# PowerSupplies_old.net
KiCad netlist of a schematic drawn in Altium Designer
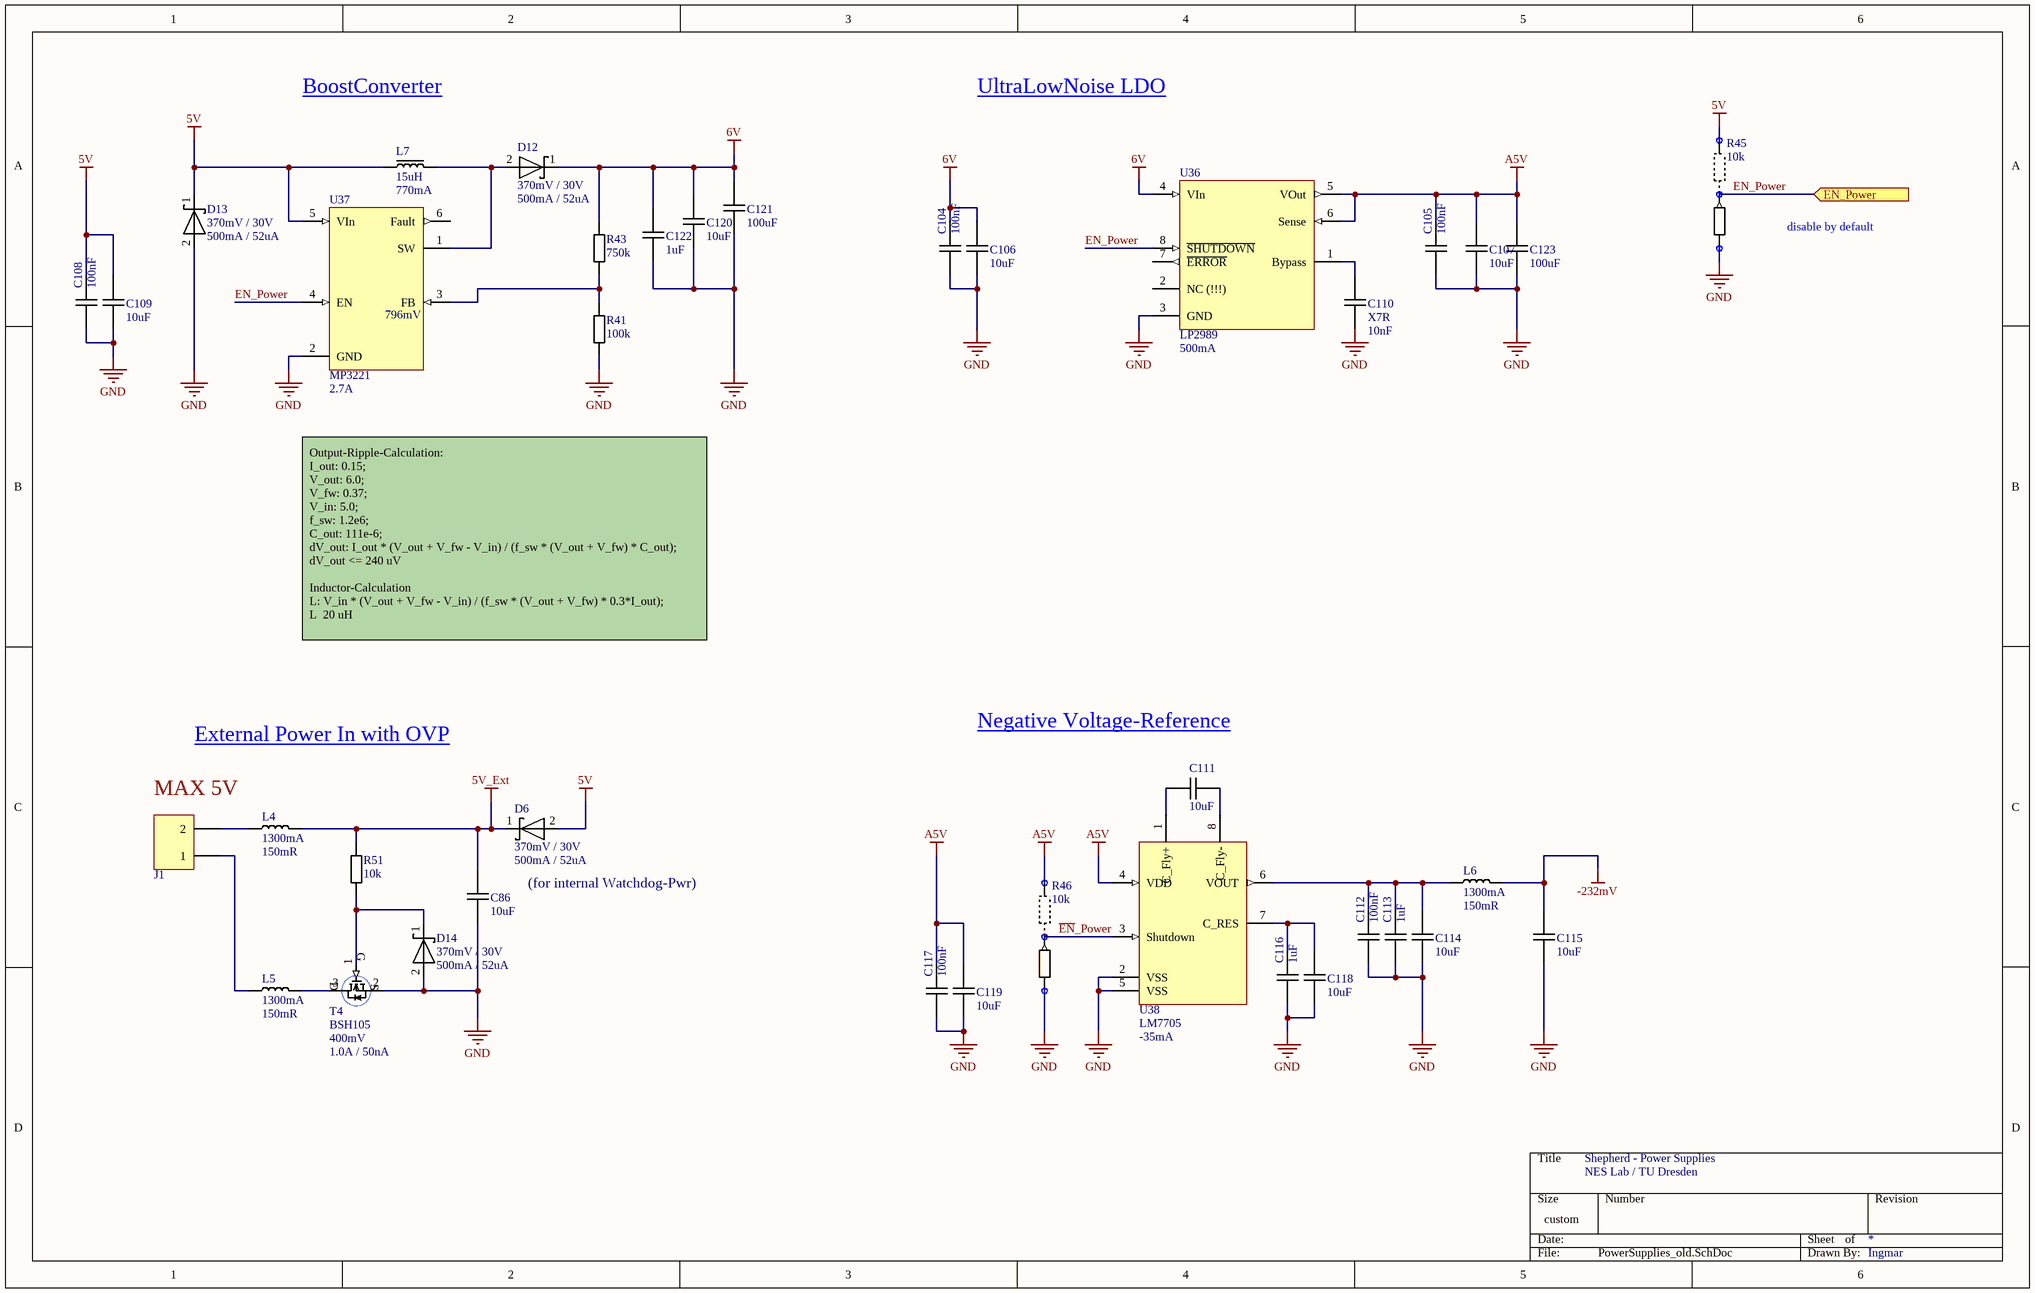
[diagram p0: PowerSupplies_old.SchDoc]

(export (version "E")
  (design (tool "Eeschema 10.0.6"))
  (components
    (comp (ref "C86")
      (value "10uF")
      (footprint "CAPC1608X09")
      (description "Capacitor")
      (fields (field (name "MANUFACTURER") "Murata") (field (name "TOLERANCE") "10%"))
      (libsource (lib "shepherd_parts") (part ".C_0603_10uF_6V3"))
    )
    (comp (ref "C104")
      (value "100nF")
      (footprint "CAPC1005X06")
      (description "Capacitor")
      (fields (field (name "MANUFACTURER") "Murata") (field (name "TOLERANCE") "10%"))
      (libsource (lib "shepherd_parts") (part ".C_0402_100nF_10V"))
    )
    (comp (ref "C105")
      (value "100nF")
      (footprint "CAPC1005X06")
      (description "Capacitor")
      (fields (field (name "MANUFACTURER") "Murata") (field (name "TOLERANCE") "10%"))
      (libsource (lib "shepherd_parts") (part ".C_0402_100nF_10V"))
    )
    (comp (ref "C106")
      (value "10uF")
      (footprint "CAPC1608X09")
      (description "Capacitor")
      (fields (field (name "MANUFACTURER") "Murata") (field (name "TOLERANCE") "10%"))
      (libsource (lib "shepherd_parts") (part ".C_0603_10uF_6V3"))
    )
    (comp (ref "C107")
      (value "10uF")
      (footprint "CAPC1608X09")
      (description "Capacitor")
      (fields (field (name "MANUFACTURER") "Murata") (field (name "TOLERANCE") "10%"))
      (libsource (lib "shepherd_parts") (part ".C_0603_10uF_6V3"))
    )
    (comp (ref "C108")
      (value "100nF")
      (footprint "CAPC1005X06")
      (description "Capacitor")
      (fields (field (name "MANUFACTURER") "Murata") (field (name "TOLERANCE") "10%"))
      (libsource (lib "shepherd_parts") (part ".C_0402_100nF_10V"))
    )
    (comp (ref "C109")
      (value "10uF")
      (footprint "CAPC1608X09")
      (description "Capacitor")
      (fields (field (name "MANUFACTURER") "Murata") (field (name "TOLERANCE") "10%"))
      (libsource (lib "shepherd_parts") (part ".C_0603_10uF_6V3"))
    )
    (comp (ref "C110")
      (value "10nF")
      (footprint "CAPC1005X06")
      (description "Capacitor")
      (fields
        (field (name "MANUFACTURER") "Murata")
        (field (name "TOLERANCE") "10%")
        (field (name "DIELECTRIC") "X7R")
      )
      (libsource (lib "shepherd_parts") (part ".C_0402_10nF_25V"))
    )
    (comp (ref "C111")
      (value "10uF")
      (footprint "CAPC1608X09")
      (description "Capacitor")
      (fields (field (name "MANUFACTURER") "Murata") (field (name "TOLERANCE") "10%"))
      (libsource (lib "shepherd_parts") (part ".C_0603_10uF_6V3"))
    )
    (comp (ref "C112")
      (value "100nF")
      (footprint "CAPC1005X06")
      (description "Capacitor")
      (fields (field (name "MANUFACTURER") "Murata") (field (name "TOLERANCE") "10%"))
      (libsource (lib "shepherd_parts") (part ".C_0402_100nF_10V"))
    )
    (comp (ref "C113")
      (value "1uF")
      (footprint "CAPC1608X09")
      (description "Capacitor")
      (fields (field (name "MANUFACTURER") "KEMET") (field (name "TOLERANCE") "10%"))
      (libsource (lib "shepherd_parts") (part ".C_0603_1uF_10V"))
    )
    (comp (ref "C114")
      (value "10uF")
      (footprint "CAPC1608X09")
      (description "Capacitor")
      (fields (field (name "MANUFACTURER") "Murata") (field (name "TOLERANCE") "10%"))
      (libsource (lib "shepherd_parts") (part ".C_0603_10uF_6V3"))
    )
    (comp (ref "C115")
      (value "10uF")
      (footprint "CAPC1608X09")
      (description "Capacitor")
      (fields (field (name "MANUFACTURER") "Murata") (field (name "TOLERANCE") "10%"))
      (libsource (lib "shepherd_parts") (part ".C_0603_10uF_6V3"))
    )
    (comp (ref "C116")
      (value "1uF")
      (footprint "CAPC1608X09")
      (description "Capacitor")
      (fields (field (name "MANUFACTURER") "KEMET") (field (name "TOLERANCE") "10%"))
      (libsource (lib "shepherd_parts") (part ".C_0603_1uF_10V"))
    )
    (comp (ref "C117")
      (value "100nF")
      (footprint "CAPC1005X06")
      (description "Capacitor")
      (fields (field (name "MANUFACTURER") "Murata") (field (name "TOLERANCE") "10%"))
      (libsource (lib "shepherd_parts") (part ".C_0402_100nF_10V"))
    )
    (comp (ref "C118")
      (value "10uF")
      (footprint "CAPC1608X09")
      (description "Capacitor")
      (fields (field (name "MANUFACTURER") "Murata") (field (name "TOLERANCE") "10%"))
      (libsource (lib "shepherd_parts") (part ".C_0603_10uF_6V3"))
    )
    (comp (ref "C119")
      (value "10uF")
      (footprint "CAPC1608X09")
      (description "Capacitor")
      (fields (field (name "MANUFACTURER") "Murata") (field (name "TOLERANCE") "10%"))
      (libsource (lib "shepherd_parts") (part ".C_0603_10uF_6V3"))
    )
    (comp (ref "C120")
      (value "10uF")
      (footprint "CAPC1608X09")
      (description "Capacitor")
      (fields (field (name "MANUFACTURER") "Murata") (field (name "TOLERANCE") "10%"))
      (libsource (lib "shepherd_parts") (part ".C_0603_10uF_6V3"))
    )
    (comp (ref "C121")
      (value "100uF")
      (footprint "CAPC3216X18")
      (description "Capacitor")
      (fields (field (name "MANUFACTURER") "Taiyo Yuden") (field (name "TOLERANCE") "20%"))
      (libsource (lib "shepherd_parts") (part ".C_1206_100uF_6V3"))
    )
    (comp (ref "C122")
      (value "1uF")
      (footprint "CAPC1608X09")
      (description "Capacitor")
      (fields (field (name "MANUFACTURER") "KEMET") (field (name "TOLERANCE") "10%"))
      (libsource (lib "shepherd_parts") (part ".C_0603_1uF_10V"))
    )
    (comp (ref "C123")
      (value "100uF")
      (footprint "CAPC3216X18")
      (description "Capacitor")
      (fields (field (name "MANUFACTURER") "Taiyo Yuden") (field (name "TOLERANCE") "20%"))
      (libsource (lib "shepherd_parts") (part ".C_1206_100uF_6V3"))
    )
    (comp (ref "D6")
      (value "370mV / 30V")
      (footprint "SODFL160X70-2N")
      (description "Diode Si, 370mV 500mA forward, 30V 52uA reverse, 3 A Surge,")
      (fields
        (field (name "MANUFACTURER") "On Semi")
        (field (name "I_MAX") "500mA / 52uA")
        (field (name "Comment") "D_SOD523_370mV_500mA")
      )
      (libsource (lib "shepherd_parts") (part ".D_SOD523_370mV_500mA"))
    )
    (comp (ref "D12")
      (value "370mV / 30V")
      (footprint "SODFL160X70-2N")
      (description "Diode Si, 370mV 500mA forward, 30V 52uA reverse, 3 A Surge,")
      (fields
        (field (name "MANUFACTURER") "On Semi")
        (field (name "I_MAX") "500mA / 52uA")
        (field (name "Comment") "D_SOD523_370mV_500mA")
      )
      (libsource (lib "shepherd_parts") (part ".D_SOD523_370mV_500mA"))
    )
    (comp (ref "D13")
      (value "370mV / 30V")
      (footprint "SODFL160X70-2N")
      (description "Diode Si, 370mV 500mA forward, 30V 52uA reverse, 3 A Surge,")
      (fields
        (field (name "MANUFACTURER") "On Semi")
        (field (name "I_MAX") "500mA / 52uA")
        (field (name "Comment") "D_SOD523_370mV_500mA")
      )
      (libsource (lib "shepherd_parts") (part ".D_SOD523_370mV_500mA"))
    )
    (comp (ref "D14")
      (value "370mV / 30V")
      (footprint "SODFL160X70-2N")
      (description "Diode Si, 370mV 500mA forward, 30V 52uA reverse, 3 A Surge,")
      (fields
        (field (name "MANUFACTURER") "On Semi")
        (field (name "I_MAX") "500mA / 52uA")
        (field (name "Comment") "D_SOD523_370mV_500mA")
      )
      (libsource (lib "shepherd_parts") (part ".D_SOD523_370mV_500mA"))
    )
    (comp (ref "J1")
      (value ".J_T1x2_3.5mm_Screw")
      (footprint "P_Phoenix_1984617")
      (description "Fixed Terminal Block, Screw")
      (fields (field (name "MANUFACTURER") "Phoenix Contact"))
      (libsource (lib "shepherd_parts") (part ".J_T1x2_3.5mm_Screw"))
    )
    (comp (ref "L4")
      (value "150mR")
      (footprint "INDC1608X08")
      (description "Ferrite Bead, 600 Ohm @ 100 MHz,")
      (fields
        (field (name "MANUFACTURER") "Murata")
        (field (name "TOLERANCE") "25 %")
        (field (name "I_MAX") "1300mA")
      )
      (libsource (lib "shepherd_parts") (part ".L_FB_0603_Z600R_1300mA"))
    )
    (comp (ref "L5")
      (value "150mR")
      (footprint "INDC1608X08")
      (description "Ferrite Bead, 600 Ohm @ 100 MHz,")
      (fields
        (field (name "MANUFACTURER") "Murata")
        (field (name "TOLERANCE") "25 %")
        (field (name "I_MAX") "1300mA")
      )
      (libsource (lib "shepherd_parts") (part ".L_FB_0603_Z600R_1300mA"))
    )
    (comp (ref "L6")
      (value "150mR")
      (footprint "INDC1608X08")
      (description "Ferrite Bead, 600 Ohm @ 100 MHz,")
      (fields
        (field (name "MANUFACTURER") "Murata")
        (field (name "TOLERANCE") "25 %")
        (field (name "I_MAX") "1300mA")
      )
      (libsource (lib "shepherd_parts") (part ".L_FB_0603_Z600R_1300mA"))
    )
    (comp (ref "L7")
      (value "15uH")
      (footprint "INDP4040X25N")
      (description "Inductor, fixed, shielded, 144 mOhm")
      (fields
        (field (name "MANUFACTURER") "Bourns")
        (field (name "TOLERANCE") "20")
        (field (name "I_MAX") "770mA")
      )
      (libsource (lib "shepherd_parts") (part ".L_SRN4026-150M"))
    )
    (comp (ref "R41")
      (value "100k")
      (footprint "RESC1005X04")
      (description "Resistor")
      (fields (field (name "MANUFACTURER") "Panasonic") (field (name "TOLERANCE") "5%"))
      (libsource (lib "shepherd_parts") (part ".R_0402_100k"))
    )
    (comp (ref "R43")
      (value "750k")
      (footprint "RESC1005X04")
      (description "Resistor")
      (fields (field (name "MANUFACTURER") "Panasonic") (field (name "TOLERANCE") "5%"))
      (libsource (lib "shepherd_parts") (part ".R_0402_750k"))
    )
    (comp (ref "R45")
      (value "10k")
      (footprint "RESC1005X04")
      (description "Resistor")
      (fields (field (name "MANUFACTURER") "Panasonic") (field (name "TOLERANCE") "5%"))
      (libsource (lib "shepherd_parts") (part ".R_0402_10k_SEL"))
    )
    (comp (ref "R46")
      (value "10k")
      (footprint "RESC1005X04")
      (description "Resistor")
      (fields (field (name "MANUFACTURER") "Panasonic") (field (name "TOLERANCE") "5%"))
      (libsource (lib "shepherd_parts") (part ".R_0402_10k_SEL"))
    )
    (comp (ref "R51")
      (value "10k")
      (footprint "RESC1005X04")
      (description "Resistor")
      (fields (field (name "MANUFACTURER") "Panasonic") (field (name "TOLERANCE") "5%"))
      (libsource (lib "shepherd_parts") (part ".R_0402_10k"))
    )
    (comp (ref "T4")
      (value "BSH105")
      (footprint "SOT65P210X100-3N SOT323")
      (fields
        (field (name "MANUFACTURER") "Nexperia")
        (field (name "V_MIN") "400mV")
        (field (name "I_MAX") "1.0A / 50nA")
      )
      (libsource (lib "shepherd_parts") (part ".T_BSH105"))
    )
    (comp (ref "U36")
      (value "LP2989")
      (footprint "TSOP65P490X110-8N")
      (description "VoltageRegulator, UltraLowNoise LDO, 5V, 500mA, 60 dB RippleRejection, 18 uV RMS Noise,")
      (fields (field (name "I_MAX") "500mA") (field (name "MANUFACTURER") "TI"))
      (libsource (lib "shepherd_parts") (part "LP2989"))
    )
    (comp (ref "U37")
      (value "MP3221")
      (footprint "SOT95P280X100-6N")
      (description "VoltageRegulator, 1.2 MHz Boost with integrated 88 mOhm Mosfet, 270 uA quiescent, 3-6V Output")
      (fields (field (name "MANUFACTURER") "MPS") (field (name "I_MAX") "2.7A"))
      (libsource (lib "shepherd_parts") (part "MP3221"))
    )
    (comp (ref "U38")
      (value "LM7705")
      (footprint "TSOP65P490X110-8N")
      (description "VoltageRegulator, -232mV Buck-Boost, 4mVpp")
      (fields (field (name "I_MAX") "-35mA") (field (name "MANUFACTURER") "TI"))
      (libsource (lib "shepherd_parts") (part "LM7705"))
    )
  )
  (nets
    (net (code "1") (name "-232mV") (class "Default")
      (node (ref "C115") (pin "2") (pinfunction "2_2") (pintype "passive"))
      (node (ref "L6") (pin "2") (pinfunction "2_2") (pintype "passive"))
    )
    (net (code "2") (name "/EN_Power") (class "Default")
      (node (ref "R45") (pin "3") (pinfunction "3_3") (pintype "output"))
      (node (ref "U36") (pin "8") (pinfunction "~{SHUTDOWN}_8") (pintype "input"))
      (node (ref "U37") (pin "4") (pinfunction "EN_4") (pintype "input"))
    )
    (net (code "3") (name "/~{EN}_Power") (class "Default")
      (node (ref "R46") (pin "3") (pinfunction "3_3") (pintype "output"))
      (node (ref "U38") (pin "3") (pinfunction "Shutdown_3") (pintype "input"))
    )
    (net (code "4") (name "5V") (class "Default")
      (node (ref "C108") (pin "2") (pinfunction "2_2") (pintype "passive"))
      (node (ref "C109") (pin "2") (pinfunction "2_2") (pintype "passive"))
      (node (ref "D13") (pin "1") (pinfunction "1_1") (pintype "passive"))
      (node (ref "D6") (pin "2") (pinfunction "2_2") (pintype "passive"))
      (node (ref "L7") (pin "1") (pinfunction "1_1") (pintype "passive"))
      (node (ref "R45") (pin "2") (pinfunction "2_2") (pintype "passive"))
      (node (ref "U37") (pin "5") (pinfunction "VIn_5") (pintype "input"))
    )
    (net (code "5") (name "5V_Ext") (class "Default")
      (node (ref "C86") (pin "2") (pinfunction "2_2") (pintype "passive"))
      (node (ref "D6") (pin "1") (pinfunction "1_1") (pintype "passive"))
      (node (ref "L4") (pin "2") (pinfunction "2_2") (pintype "passive"))
      (node (ref "R51") (pin "2") (pinfunction "2_2") (pintype "passive"))
    )
    (net (code "6") (name "6V") (class "Default")
      (node (ref "C104") (pin "2") (pinfunction "2_2") (pintype "passive"))
      (node (ref "C106") (pin "2") (pinfunction "2_2") (pintype "passive"))
      (node (ref "C120") (pin "2") (pinfunction "2_2") (pintype "passive"))
      (node (ref "C121") (pin "2") (pinfunction "2_2") (pintype "passive"))
      (node (ref "C122") (pin "2") (pinfunction "2_2") (pintype "passive"))
      (node (ref "D12") (pin "1") (pinfunction "1_1") (pintype "passive"))
      (node (ref "R43") (pin "2") (pinfunction "2_2") (pintype "passive"))
      (node (ref "U36") (pin "4") (pinfunction "VIn_4") (pintype "input"))
    )
    (net (code "7") (name "A5V") (class "Default")
      (node (ref "C105") (pin "2") (pinfunction "2_2") (pintype "passive"))
      (node (ref "C107") (pin "2") (pinfunction "2_2") (pintype "passive"))
      (node (ref "C117") (pin "2") (pinfunction "2_2") (pintype "passive"))
      (node (ref "C119") (pin "2") (pinfunction "2_2") (pintype "passive"))
      (node (ref "C123") (pin "2") (pinfunction "2_2") (pintype "passive"))
      (node (ref "R46") (pin "2") (pinfunction "2_2") (pintype "passive"))
      (node (ref "U36") (pin "5") (pinfunction "VOut_5") (pintype "output"))
      (node (ref "U36") (pin "6") (pinfunction "Sense_6") (pintype "input"))
      (node (ref "U38") (pin "4") (pinfunction "VDD_4") (pintype "input"))
    )
    (net (code "8") (name "GND") (class "Default")
      (node (ref "C104") (pin "1") (pinfunction "1_1") (pintype "passive"))
      (node (ref "C105") (pin "1") (pinfunction "1_1") (pintype "passive"))
      (node (ref "C106") (pin "1") (pinfunction "1_1") (pintype "passive"))
      (node (ref "C107") (pin "1") (pinfunction "1_1") (pintype "passive"))
      (node (ref "C108") (pin "1") (pinfunction "1_1") (pintype "passive"))
      (node (ref "C109") (pin "1") (pinfunction "1_1") (pintype "passive"))
      (node (ref "C110") (pin "1") (pinfunction "1_1") (pintype "passive"))
      (node (ref "C112") (pin "1") (pinfunction "1_1") (pintype "passive"))
      (node (ref "C113") (pin "1") (pinfunction "1_1") (pintype "passive"))
      (node (ref "C114") (pin "1") (pinfunction "1_1") (pintype "passive"))
      (node (ref "C115") (pin "1") (pinfunction "1_1") (pintype "passive"))
      (node (ref "C116") (pin "1") (pinfunction "1_1") (pintype "passive"))
      (node (ref "C117") (pin "1") (pinfunction "1_1") (pintype "passive"))
      (node (ref "C118") (pin "1") (pinfunction "1_1") (pintype "passive"))
      (node (ref "C119") (pin "1") (pinfunction "1_1") (pintype "passive"))
      (node (ref "C120") (pin "1") (pinfunction "1_1") (pintype "passive"))
      (node (ref "C121") (pin "1") (pinfunction "1_1") (pintype "passive"))
      (node (ref "C122") (pin "1") (pinfunction "1_1") (pintype "passive"))
      (node (ref "C123") (pin "1") (pinfunction "1_1") (pintype "passive"))
      (node (ref "C86") (pin "1") (pinfunction "1_1") (pintype "passive"))
      (node (ref "D13") (pin "2") (pinfunction "2_2") (pintype "passive"))
      (node (ref "D14") (pin "2") (pinfunction "2_2") (pintype "passive"))
      (node (ref "R41") (pin "1") (pinfunction "1_1") (pintype "passive"))
      (node (ref "R45") (pin "1") (pinfunction "1_1") (pintype "passive"))
      (node (ref "R46") (pin "1") (pinfunction "1_1") (pintype "passive"))
      (node (ref "T4") (pin "2") (pinfunction "S_2") (pintype "passive"))
      (node (ref "U36") (pin "3") (pinfunction "GND_3") (pintype "power_in"))
      (node (ref "U37") (pin "2") (pinfunction "GND_2") (pintype "power_in"))
      (node (ref "U38") (pin "2") (pinfunction "VSS_2") (pintype "power_in"))
      (node (ref "U38") (pin "5") (pinfunction "VSS_5") (pintype "power_in"))
    )
    (net (code "9") (name "Net-(J1-Pad1)") (class "Default")
      (node (ref "J1") (pin "1") (pinfunction "1_1") (pintype "passive"))
      (node (ref "L5") (pin "1") (pinfunction "1_1") (pintype "passive"))
    )
    (net (code "10") (name "Net-(J1-Pad2)") (class "Default")
      (node (ref "J1") (pin "2") (pinfunction "2_2") (pintype "passive"))
      (node (ref "L4") (pin "1") (pinfunction "1_1") (pintype "passive"))
    )
    (net (code "11") (name "Net-(T4-D)") (class "Default")
      (node (ref "L5") (pin "2") (pinfunction "2_2") (pintype "passive"))
      (node (ref "T4") (pin "3") (pinfunction "D_3") (pintype "passive"))
    )
    (net (code "12") (name "Net-(T4-G)") (class "Default")
      (node (ref "D14") (pin "1") (pinfunction "1_1") (pintype "passive"))
      (node (ref "R51") (pin "1") (pinfunction "1_1") (pintype "passive"))
      (node (ref "T4") (pin "1") (pinfunction "G_1") (pintype "input"))
    )
    (net (code "13") (name "Net-(U36-Bypass)") (class "Default")
      (node (ref "C110") (pin "2") (pinfunction "2_2") (pintype "passive"))
      (node (ref "U36") (pin "1") (pinfunction "Bypass_1") (pintype "power_in"))
    )
    (net (code "14") (name "Net-(U37-FB)") (class "Default")
      (node (ref "R41") (pin "2") (pinfunction "2_2") (pintype "passive"))
      (node (ref "R43") (pin "1") (pinfunction "1_1") (pintype "passive"))
      (node (ref "U37") (pin "3") (pinfunction "FB_3") (pintype "input"))
    )
    (net (code "15") (name "Net-(U37-SW)") (class "Default")
      (node (ref "D12") (pin "2") (pinfunction "2_2") (pintype "passive"))
      (node (ref "L7") (pin "2") (pinfunction "2_2") (pintype "passive"))
      (node (ref "U37") (pin "1") (pinfunction "SW_1") (pintype "power_in"))
    )
    (net (code "16") (name "Net-(U38-C_Fly+)") (class "Default")
      (node (ref "C111") (pin "2") (pinfunction "2_2") (pintype "passive"))
      (node (ref "U38") (pin "1") (pinfunction "C_Fly+_1") (pintype "power_in"))
    )
    (net (code "17") (name "Net-(U38-C_Fly-)") (class "Default")
      (node (ref "C111") (pin "1") (pinfunction "1_1") (pintype "passive"))
      (node (ref "U38") (pin "8") (pinfunction "C_Fly-_8") (pintype "power_in"))
    )
    (net (code "18") (name "Net-(U38-C_RES)") (class "Default")
      (node (ref "C116") (pin "2") (pinfunction "2_2") (pintype "passive"))
      (node (ref "C118") (pin "2") (pinfunction "2_2") (pintype "passive"))
      (node (ref "U38") (pin "7") (pinfunction "C_RES_7") (pintype "power_in"))
    )
    (net (code "19") (name "Net-(U38-VOUT)") (class "Default")
      (node (ref "C112") (pin "2") (pinfunction "2_2") (pintype "passive"))
      (node (ref "C113") (pin "2") (pinfunction "2_2") (pintype "passive"))
      (node (ref "C114") (pin "2") (pinfunction "2_2") (pintype "passive"))
      (node (ref "L6") (pin "1") (pinfunction "1_1") (pintype "passive"))
      (node (ref "U38") (pin "6") (pinfunction "VOUT_6") (pintype "output"))
    )
    (net (code "20") (name "unconnected-(U36-NC_(!!!)-Pad2)") (class "Default")
      (node (ref "U36") (pin "2") (pinfunction "NC_(!!!)_2") (pintype "passive"))
    )
    (net (code "21") (name "unconnected-(U36-~{ERROR}-Pad7)") (class "Default")
      (node (ref "U36") (pin "7") (pinfunction "~{ERROR}_7") (pintype "output"))
    )
    (net (code "22") (name "unconnected-(U37-Fault-Pad6)") (class "Default")
      (node (ref "U37") (pin "6") (pinfunction "Fault_6") (pintype "output"))
    )
  )
)
